# ToolHead.net
KiCad netlist of a schematic drawn in EAGLE
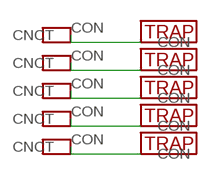
[diagram p0: schematic, sheet 1]

(export (version "E")
  (design (tool "Eeschema 10.0.6"))
  (components
    (comp (ref "U$1")
      (value "MOLEX-LITE-TRAP")
      (footprint "eagle-import:MOLEX-LITE-TRAP")
      (libsource (lib "eagle-import") (part "MOLEX-LITE-TRAP"))
    )
    (comp (ref "U$2")
      (value "MOLEX-LITE-TRAP")
      (footprint "eagle-import:MOLEX-LITE-TRAP")
      (libsource (lib "eagle-import") (part "MOLEX-LITE-TRAP"))
    )
    (comp (ref "U$3")
      (value "MOLEX-LITE-TRAP")
      (footprint "eagle-import:MOLEX-LITE-TRAP")
      (libsource (lib "eagle-import") (part "MOLEX-LITE-TRAP"))
    )
    (comp (ref "U$4")
      (value "MOLEX-LITE-TRAP")
      (footprint "eagle-import:MOLEX-LITE-TRAP")
      (libsource (lib "eagle-import") (part "MOLEX-LITE-TRAP"))
    )
    (comp (ref "U$5")
      (value "MOLEX-LITE-TRAP")
      (footprint "eagle-import:MOLEX-LITE-TRAP")
      (libsource (lib "eagle-import") (part "MOLEX-LITE-TRAP"))
    )
    (comp (ref "U$6")
      (value "SPRING-FINGER")
      (footprint "eagle-import:SPRING-FINGER")
      (libsource (lib "eagle-import") (part "SPRING-FINGER"))
    )
    (comp (ref "U$7")
      (value "SPRING-FINGER")
      (footprint "eagle-import:SPRING-FINGER")
      (libsource (lib "eagle-import") (part "SPRING-FINGER"))
    )
    (comp (ref "U$8")
      (value "SPRING-FINGER")
      (footprint "eagle-import:SPRING-FINGER")
      (libsource (lib "eagle-import") (part "SPRING-FINGER"))
    )
    (comp (ref "U$9")
      (value "SPRING-FINGER")
      (footprint "eagle-import:SPRING-FINGER")
      (libsource (lib "eagle-import") (part "SPRING-FINGER"))
    )
    (comp (ref "U$10")
      (value "SPRING-FINGER")
      (footprint "eagle-import:SPRING-FINGER")
      (libsource (lib "eagle-import") (part "SPRING-FINGER"))
    )
  )
  (nets
    (net (code "1") (name "Net-(U$1-CON)") (class "Default")
      (node (ref "U$1") (pin "TRAP") (pinfunction "CON_TRAP") (pintype "bidirectional"))
      (node (ref "U$7") (pin "CON") (pinfunction "CNCT_CON") (pintype "bidirectional"))
    )
    (net (code "2") (name "Net-(U$2-CON)") (class "Default")
      (node (ref "U$2") (pin "TRAP") (pinfunction "CON_TRAP") (pintype "bidirectional"))
      (node (ref "U$8") (pin "CON") (pinfunction "CNCT_CON") (pintype "bidirectional"))
    )
    (net (code "3") (name "Net-(U$3-CON)") (class "Default")
      (node (ref "U$3") (pin "TRAP") (pinfunction "CON_TRAP") (pintype "bidirectional"))
      (node (ref "U$9") (pin "CON") (pinfunction "CNCT_CON") (pintype "bidirectional"))
    )
    (net (code "4") (name "Net-(U$5-CON)") (class "Default")
      (node (ref "U$5") (pin "TRAP") (pinfunction "CON_TRAP") (pintype "bidirectional"))
      (node (ref "U$6") (pin "CON") (pinfunction "CNCT_CON") (pintype "bidirectional"))
    )
    (net (code "5") (name "Net-(U$10-CNCT)") (class "Default")
      (node (ref "U$10") (pin "CON") (pinfunction "CNCT_CON") (pintype "bidirectional"))
      (node (ref "U$4") (pin "TRAP") (pinfunction "CON_TRAP") (pintype "bidirectional"))
    )
  )
)
